# Main_Board.net
KiCad netlist of a schematic drawn in EAGLE
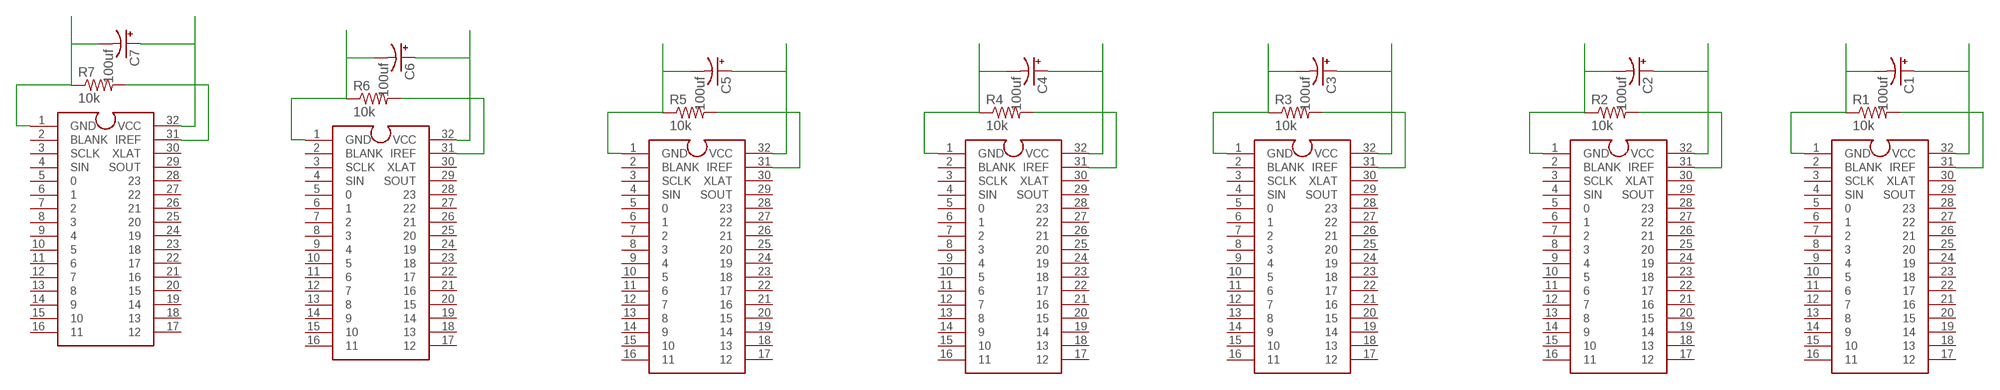
[diagram p0: schematic, sheet 1]

(export (version "E")
  (design (tool "Eeschema 10.0.6"))
  (components
    (comp (ref "C1")
      (value "100uf")
      (footprint "eagle-import:E2,5-6")
      (libsource (lib "eagle-import") (part "CPOL-USE2.5-6"))
    )
    (comp (ref "C2")
      (value "100uf")
      (footprint "eagle-import:E2,5-6")
      (libsource (lib "eagle-import") (part "CPOL-USE2.5-6"))
    )
    (comp (ref "C3")
      (value "100uf")
      (footprint "eagle-import:E2,5-6")
      (libsource (lib "eagle-import") (part "CPOL-USE2.5-6"))
    )
    (comp (ref "C4")
      (value "100uf")
      (footprint "eagle-import:E2,5-6")
      (libsource (lib "eagle-import") (part "CPOL-USE2.5-6"))
    )
    (comp (ref "C5")
      (value "100uf")
      (footprint "eagle-import:E2,5-6")
      (libsource (lib "eagle-import") (part "CPOL-USE2.5-6"))
    )
    (comp (ref "C6")
      (value "100uf")
      (footprint "eagle-import:E2,5-6")
      (libsource (lib "eagle-import") (part "CPOL-USE2.5-6"))
    )
    (comp (ref "C7")
      (value "100uf")
      (footprint "eagle-import:E2,5-6")
      (libsource (lib "eagle-import") (part "CPOL-USE2.5-6"))
    )
    (comp (ref "R1")
      (value "10k")
      (footprint "eagle-import:0207_10")
      (libsource (lib "eagle-import") (part "R-US_0207/10"))
    )
    (comp (ref "R2")
      (value "10k")
      (footprint "eagle-import:0207_10")
      (libsource (lib "eagle-import") (part "R-US_0207/10"))
    )
    (comp (ref "R3")
      (value "10k")
      (footprint "eagle-import:0207_10")
      (libsource (lib "eagle-import") (part "R-US_0207/10"))
    )
    (comp (ref "R4")
      (value "10k")
      (footprint "eagle-import:0207_10")
      (libsource (lib "eagle-import") (part "R-US_0207/10"))
    )
    (comp (ref "R5")
      (value "10k")
      (footprint "eagle-import:0207_10")
      (libsource (lib "eagle-import") (part "R-US_0207/10"))
    )
    (comp (ref "R6")
      (value "10k")
      (footprint "eagle-import:0207_10")
      (libsource (lib "eagle-import") (part "R-US_0207/10"))
    )
    (comp (ref "R7")
      (value "10k")
      (footprint "eagle-import:0207_10")
      (libsource (lib "eagle-import") (part "R-US_0207/10"))
    )
    (comp (ref "U$1")
      (value "TLC5947DAC")
      (footprint "eagle-import:DAP38")
      (libsource (lib "eagle-import") (part "TLC5947DAC"))
    )
    (comp (ref "U$2")
      (value "TLC5947DAC")
      (footprint "eagle-import:DAP38")
      (libsource (lib "eagle-import") (part "TLC5947DAC"))
    )
    (comp (ref "U$3")
      (value "TLC5947DAC")
      (footprint "eagle-import:DAP38")
      (libsource (lib "eagle-import") (part "TLC5947DAC"))
    )
    (comp (ref "U$4")
      (value "TLC5947DAC")
      (footprint "eagle-import:DAP38")
      (libsource (lib "eagle-import") (part "TLC5947DAC"))
    )
    (comp (ref "U$5")
      (value "TLC5947DAC")
      (footprint "eagle-import:DAP38")
      (libsource (lib "eagle-import") (part "TLC5947DAC"))
    )
    (comp (ref "U$6")
      (value "TLC5947DAC")
      (footprint "eagle-import:DAP38")
      (libsource (lib "eagle-import") (part "TLC5947DAC"))
    )
    (comp (ref "U$7")
      (value "TLC5947DAC")
      (footprint "eagle-import:DAP38")
      (libsource (lib "eagle-import") (part "TLC5947DAC"))
    )
  )
  (nets
    (net (code "1") (name "Net-(U$1-GND)") (class "Default")
      (node (ref "C1") (pin "-") (pinfunction "-_-") (pintype "passive"))
      (node (ref "R1") (pin "1") (pinfunction "1_1") (pintype "passive"))
      (node (ref "U$1") (pin "1") (pinfunction "GND_1") (pintype "bidirectional"))
    )
    (net (code "2") (name "Net-(U$1-IREF)") (class "Default")
      (node (ref "R1") (pin "2") (pinfunction "2_2") (pintype "passive"))
      (node (ref "U$1") (pin "31") (pinfunction "IREF_31") (pintype "bidirectional"))
    )
    (net (code "3") (name "Net-(U$1-VCC)") (class "Default")
      (node (ref "C1") (pin "+") (pinfunction "+_+") (pintype "passive"))
      (node (ref "U$1") (pin "32") (pinfunction "VCC_32") (pintype "bidirectional"))
    )
    (net (code "4") (name "Net-(U$2-GND)") (class "Default")
      (node (ref "C2") (pin "-") (pinfunction "-_-") (pintype "passive"))
      (node (ref "R2") (pin "1") (pinfunction "1_1") (pintype "passive"))
      (node (ref "U$2") (pin "1") (pinfunction "GND_1") (pintype "bidirectional"))
    )
    (net (code "5") (name "Net-(U$2-IREF)") (class "Default")
      (node (ref "R2") (pin "2") (pinfunction "2_2") (pintype "passive"))
      (node (ref "U$2") (pin "31") (pinfunction "IREF_31") (pintype "bidirectional"))
    )
    (net (code "6") (name "Net-(U$2-VCC)") (class "Default")
      (node (ref "C2") (pin "+") (pinfunction "+_+") (pintype "passive"))
      (node (ref "U$2") (pin "32") (pinfunction "VCC_32") (pintype "bidirectional"))
    )
    (net (code "7") (name "Net-(U$3-GND)") (class "Default")
      (node (ref "C3") (pin "-") (pinfunction "-_-") (pintype "passive"))
      (node (ref "R3") (pin "1") (pinfunction "1_1") (pintype "passive"))
      (node (ref "U$3") (pin "1") (pinfunction "GND_1") (pintype "bidirectional"))
    )
    (net (code "8") (name "Net-(U$3-IREF)") (class "Default")
      (node (ref "R3") (pin "2") (pinfunction "2_2") (pintype "passive"))
      (node (ref "U$3") (pin "31") (pinfunction "IREF_31") (pintype "bidirectional"))
    )
    (net (code "9") (name "Net-(U$3-VCC)") (class "Default")
      (node (ref "C3") (pin "+") (pinfunction "+_+") (pintype "passive"))
      (node (ref "U$3") (pin "32") (pinfunction "VCC_32") (pintype "bidirectional"))
    )
    (net (code "10") (name "Net-(U$4-GND)") (class "Default")
      (node (ref "C4") (pin "-") (pinfunction "-_-") (pintype "passive"))
      (node (ref "R4") (pin "1") (pinfunction "1_1") (pintype "passive"))
      (node (ref "U$4") (pin "1") (pinfunction "GND_1") (pintype "bidirectional"))
    )
    (net (code "11") (name "Net-(U$4-IREF)") (class "Default")
      (node (ref "R4") (pin "2") (pinfunction "2_2") (pintype "passive"))
      (node (ref "U$4") (pin "31") (pinfunction "IREF_31") (pintype "bidirectional"))
    )
    (net (code "12") (name "Net-(U$4-VCC)") (class "Default")
      (node (ref "C4") (pin "+") (pinfunction "+_+") (pintype "passive"))
      (node (ref "U$4") (pin "32") (pinfunction "VCC_32") (pintype "bidirectional"))
    )
    (net (code "13") (name "Net-(U$5-GND)") (class "Default")
      (node (ref "C5") (pin "-") (pinfunction "-_-") (pintype "passive"))
      (node (ref "R5") (pin "1") (pinfunction "1_1") (pintype "passive"))
      (node (ref "U$5") (pin "1") (pinfunction "GND_1") (pintype "bidirectional"))
    )
    (net (code "14") (name "Net-(U$5-IREF)") (class "Default")
      (node (ref "R5") (pin "2") (pinfunction "2_2") (pintype "passive"))
      (node (ref "U$5") (pin "31") (pinfunction "IREF_31") (pintype "bidirectional"))
    )
    (net (code "15") (name "Net-(U$5-VCC)") (class "Default")
      (node (ref "C5") (pin "+") (pinfunction "+_+") (pintype "passive"))
      (node (ref "U$5") (pin "32") (pinfunction "VCC_32") (pintype "bidirectional"))
    )
    (net (code "16") (name "Net-(U$6-GND)") (class "Default")
      (node (ref "C6") (pin "-") (pinfunction "-_-") (pintype "passive"))
      (node (ref "R6") (pin "1") (pinfunction "1_1") (pintype "passive"))
      (node (ref "U$6") (pin "1") (pinfunction "GND_1") (pintype "bidirectional"))
    )
    (net (code "17") (name "Net-(U$6-IREF)") (class "Default")
      (node (ref "R6") (pin "2") (pinfunction "2_2") (pintype "passive"))
      (node (ref "U$6") (pin "31") (pinfunction "IREF_31") (pintype "bidirectional"))
    )
    (net (code "18") (name "Net-(U$6-VCC)") (class "Default")
      (node (ref "C6") (pin "+") (pinfunction "+_+") (pintype "passive"))
      (node (ref "U$6") (pin "32") (pinfunction "VCC_32") (pintype "bidirectional"))
    )
    (net (code "19") (name "Net-(U$7-GND)") (class "Default")
      (node (ref "C7") (pin "-") (pinfunction "-_-") (pintype "passive"))
      (node (ref "R7") (pin "1") (pinfunction "1_1") (pintype "passive"))
      (node (ref "U$7") (pin "1") (pinfunction "GND_1") (pintype "bidirectional"))
    )
    (net (code "20") (name "Net-(U$7-IREF)") (class "Default")
      (node (ref "R7") (pin "2") (pinfunction "2_2") (pintype "passive"))
      (node (ref "U$7") (pin "31") (pinfunction "IREF_31") (pintype "bidirectional"))
    )
    (net (code "21") (name "Net-(U$7-VCC)") (class "Default")
      (node (ref "C7") (pin "+") (pinfunction "+_+") (pintype "passive"))
      (node (ref "U$7") (pin "32") (pinfunction "VCC_32") (pintype "bidirectional"))
    )
    (net (code "22") (name "unconnected-(U$1-0-Pad5)") (class "Default")
      (node (ref "U$1") (pin "5") (pinfunction "0_5") (pintype "bidirectional"))
    )
    (net (code "23") (name "unconnected-(U$1-1-Pad6)") (class "Default")
      (node (ref "U$1") (pin "6") (pinfunction "1_6") (pintype "bidirectional"))
    )
    (net (code "24") (name "unconnected-(U$1-2-Pad7)") (class "Default")
      (node (ref "U$1") (pin "7") (pinfunction "2_7") (pintype "bidirectional"))
    )
    (net (code "25") (name "unconnected-(U$1-3-Pad8)") (class "Default")
      (node (ref "U$1") (pin "8") (pinfunction "3_8") (pintype "bidirectional"))
    )
    (net (code "26") (name "unconnected-(U$1-4-Pad9)") (class "Default")
      (node (ref "U$1") (pin "9") (pinfunction "4_9") (pintype "bidirectional"))
    )
    (net (code "27") (name "unconnected-(U$1-5-Pad10)") (class "Default")
      (node (ref "U$1") (pin "10") (pinfunction "5_10") (pintype "bidirectional"))
    )
    (net (code "28") (name "unconnected-(U$1-6-Pad11)") (class "Default")
      (node (ref "U$1") (pin "11") (pinfunction "6_11") (pintype "bidirectional"))
    )
    (net (code "29") (name "unconnected-(U$1-7-Pad12)") (class "Default")
      (node (ref "U$1") (pin "12") (pinfunction "7_12") (pintype "bidirectional"))
    )
    (net (code "30") (name "unconnected-(U$1-8-Pad13)") (class "Default")
      (node (ref "U$1") (pin "13") (pinfunction "8_13") (pintype "bidirectional"))
    )
    (net (code "31") (name "unconnected-(U$1-9-Pad14)") (class "Default")
      (node (ref "U$1") (pin "14") (pinfunction "9_14") (pintype "bidirectional"))
    )
    (net (code "32") (name "unconnected-(U$1-10-Pad15)") (class "Default")
      (node (ref "U$1") (pin "15") (pinfunction "10_15") (pintype "bidirectional"))
    )
    (net (code "33") (name "unconnected-(U$1-11-Pad16)") (class "Default")
      (node (ref "U$1") (pin "16") (pinfunction "11_16") (pintype "bidirectional"))
    )
    (net (code "34") (name "unconnected-(U$1-12-Pad17)") (class "Default")
      (node (ref "U$1") (pin "17") (pinfunction "12_17") (pintype "bidirectional"))
    )
    (net (code "35") (name "unconnected-(U$1-13-Pad18)") (class "Default")
      (node (ref "U$1") (pin "18") (pinfunction "13_18") (pintype "bidirectional"))
    )
    (net (code "36") (name "unconnected-(U$1-14-Pad19)") (class "Default")
      (node (ref "U$1") (pin "19") (pinfunction "14_19") (pintype "bidirectional"))
    )
    (net (code "37") (name "unconnected-(U$1-15-Pad20)") (class "Default")
      (node (ref "U$1") (pin "20") (pinfunction "15_20") (pintype "bidirectional"))
    )
    (net (code "38") (name "unconnected-(U$1-16-Pad21)") (class "Default")
      (node (ref "U$1") (pin "21") (pinfunction "16_21") (pintype "bidirectional"))
    )
    (net (code "39") (name "unconnected-(U$1-17-Pad22)") (class "Default")
      (node (ref "U$1") (pin "22") (pinfunction "17_22") (pintype "bidirectional"))
    )
    (net (code "40") (name "unconnected-(U$1-18-Pad23)") (class "Default")
      (node (ref "U$1") (pin "23") (pinfunction "18_23") (pintype "bidirectional"))
    )
    (net (code "41") (name "unconnected-(U$1-19-Pad24)") (class "Default")
      (node (ref "U$1") (pin "24") (pinfunction "19_24") (pintype "bidirectional"))
    )
    (net (code "42") (name "unconnected-(U$1-20-Pad25)") (class "Default")
      (node (ref "U$1") (pin "25") (pinfunction "20_25") (pintype "bidirectional"))
    )
    (net (code "43") (name "unconnected-(U$1-21-Pad26)") (class "Default")
      (node (ref "U$1") (pin "26") (pinfunction "21_26") (pintype "bidirectional"))
    )
    (net (code "44") (name "unconnected-(U$1-22-Pad27)") (class "Default")
      (node (ref "U$1") (pin "27") (pinfunction "22_27") (pintype "bidirectional"))
    )
    (net (code "45") (name "unconnected-(U$1-23-Pad28)") (class "Default")
      (node (ref "U$1") (pin "28") (pinfunction "23_28") (pintype "bidirectional"))
    )
    (net (code "46") (name "unconnected-(U$1-BLANK-Pad2)") (class "Default")
      (node (ref "U$1") (pin "2") (pinfunction "BLANK_2") (pintype "bidirectional"))
    )
    (net (code "47") (name "unconnected-(U$1-SCLK-Pad3)") (class "Default")
      (node (ref "U$1") (pin "3") (pinfunction "SCLK_3") (pintype "bidirectional"))
    )
    (net (code "48") (name "unconnected-(U$1-SIN-Pad4)") (class "Default")
      (node (ref "U$1") (pin "4") (pinfunction "SIN_4") (pintype "bidirectional"))
    )
    (net (code "49") (name "unconnected-(U$1-SOUT-Pad29)") (class "Default")
      (node (ref "U$1") (pin "29") (pinfunction "SOUT_29") (pintype "bidirectional"))
    )
    (net (code "50") (name "unconnected-(U$1-XLAT-Pad30)") (class "Default")
      (node (ref "U$1") (pin "30") (pinfunction "XLAT_30") (pintype "bidirectional"))
    )
    (net (code "51") (name "unconnected-(U$2-0-Pad5)") (class "Default")
      (node (ref "U$2") (pin "5") (pinfunction "0_5") (pintype "bidirectional"))
    )
    (net (code "52") (name "unconnected-(U$2-1-Pad6)") (class "Default")
      (node (ref "U$2") (pin "6") (pinfunction "1_6") (pintype "bidirectional"))
    )
    (net (code "53") (name "unconnected-(U$2-2-Pad7)") (class "Default")
      (node (ref "U$2") (pin "7") (pinfunction "2_7") (pintype "bidirectional"))
    )
    (net (code "54") (name "unconnected-(U$2-3-Pad8)") (class "Default")
      (node (ref "U$2") (pin "8") (pinfunction "3_8") (pintype "bidirectional"))
    )
    (net (code "55") (name "unconnected-(U$2-4-Pad9)") (class "Default")
      (node (ref "U$2") (pin "9") (pinfunction "4_9") (pintype "bidirectional"))
    )
    (net (code "56") (name "unconnected-(U$2-5-Pad10)") (class "Default")
      (node (ref "U$2") (pin "10") (pinfunction "5_10") (pintype "bidirectional"))
    )
    (net (code "57") (name "unconnected-(U$2-6-Pad11)") (class "Default")
      (node (ref "U$2") (pin "11") (pinfunction "6_11") (pintype "bidirectional"))
    )
    (net (code "58") (name "unconnected-(U$2-7-Pad12)") (class "Default")
      (node (ref "U$2") (pin "12") (pinfunction "7_12") (pintype "bidirectional"))
    )
    (net (code "59") (name "unconnected-(U$2-8-Pad13)") (class "Default")
      (node (ref "U$2") (pin "13") (pinfunction "8_13") (pintype "bidirectional"))
    )
    (net (code "60") (name "unconnected-(U$2-9-Pad14)") (class "Default")
      (node (ref "U$2") (pin "14") (pinfunction "9_14") (pintype "bidirectional"))
    )
    (net (code "61") (name "unconnected-(U$2-10-Pad15)") (class "Default")
      (node (ref "U$2") (pin "15") (pinfunction "10_15") (pintype "bidirectional"))
    )
    (net (code "62") (name "unconnected-(U$2-11-Pad16)") (class "Default")
      (node (ref "U$2") (pin "16") (pinfunction "11_16") (pintype "bidirectional"))
    )
    (net (code "63") (name "unconnected-(U$2-12-Pad17)") (class "Default")
      (node (ref "U$2") (pin "17") (pinfunction "12_17") (pintype "bidirectional"))
    )
    (net (code "64") (name "unconnected-(U$2-13-Pad18)") (class "Default")
      (node (ref "U$2") (pin "18") (pinfunction "13_18") (pintype "bidirectional"))
    )
    (net (code "65") (name "unconnected-(U$2-14-Pad19)") (class "Default")
      (node (ref "U$2") (pin "19") (pinfunction "14_19") (pintype "bidirectional"))
    )
    (net (code "66") (name "unconnected-(U$2-15-Pad20)") (class "Default")
      (node (ref "U$2") (pin "20") (pinfunction "15_20") (pintype "bidirectional"))
    )
    (net (code "67") (name "unconnected-(U$2-16-Pad21)") (class "Default")
      (node (ref "U$2") (pin "21") (pinfunction "16_21") (pintype "bidirectional"))
    )
    (net (code "68") (name "unconnected-(U$2-17-Pad22)") (class "Default")
      (node (ref "U$2") (pin "22") (pinfunction "17_22") (pintype "bidirectional"))
    )
    (net (code "69") (name "unconnected-(U$2-18-Pad23)") (class "Default")
      (node (ref "U$2") (pin "23") (pinfunction "18_23") (pintype "bidirectional"))
    )
    (net (code "70") (name "unconnected-(U$2-19-Pad24)") (class "Default")
      (node (ref "U$2") (pin "24") (pinfunction "19_24") (pintype "bidirectional"))
    )
    (net (code "71") (name "unconnected-(U$2-20-Pad25)") (class "Default")
      (node (ref "U$2") (pin "25") (pinfunction "20_25") (pintype "bidirectional"))
    )
    (net (code "72") (name "unconnected-(U$2-21-Pad26)") (class "Default")
      (node (ref "U$2") (pin "26") (pinfunction "21_26") (pintype "bidirectional"))
    )
    (net (code "73") (name "unconnected-(U$2-22-Pad27)") (class "Default")
      (node (ref "U$2") (pin "27") (pinfunction "22_27") (pintype "bidirectional"))
    )
    (net (code "74") (name "unconnected-(U$2-23-Pad28)") (class "Default")
      (node (ref "U$2") (pin "28") (pinfunction "23_28") (pintype "bidirectional"))
    )
    (net (code "75") (name "unconnected-(U$2-BLANK-Pad2)") (class "Default")
      (node (ref "U$2") (pin "2") (pinfunction "BLANK_2") (pintype "bidirectional"))
    )
    (net (code "76") (name "unconnected-(U$2-SCLK-Pad3)") (class "Default")
      (node (ref "U$2") (pin "3") (pinfunction "SCLK_3") (pintype "bidirectional"))
    )
    (net (code "77") (name "unconnected-(U$2-SIN-Pad4)") (class "Default")
      (node (ref "U$2") (pin "4") (pinfunction "SIN_4") (pintype "bidirectional"))
    )
    (net (code "78") (name "unconnected-(U$2-SOUT-Pad29)") (class "Default")
      (node (ref "U$2") (pin "29") (pinfunction "SOUT_29") (pintype "bidirectional"))
    )
    (net (code "79") (name "unconnected-(U$2-XLAT-Pad30)") (class "Default")
      (node (ref "U$2") (pin "30") (pinfunction "XLAT_30") (pintype "bidirectional"))
    )
    (net (code "80") (name "unconnected-(U$3-0-Pad5)") (class "Default")
      (node (ref "U$3") (pin "5") (pinfunction "0_5") (pintype "bidirectional"))
    )
    (net (code "81") (name "unconnected-(U$3-1-Pad6)") (class "Default")
      (node (ref "U$3") (pin "6") (pinfunction "1_6") (pintype "bidirectional"))
    )
    (net (code "82") (name "unconnected-(U$3-2-Pad7)") (class "Default")
      (node (ref "U$3") (pin "7") (pinfunction "2_7") (pintype "bidirectional"))
    )
    (net (code "83") (name "unconnected-(U$3-3-Pad8)") (class "Default")
      (node (ref "U$3") (pin "8") (pinfunction "3_8") (pintype "bidirectional"))
    )
    (net (code "84") (name "unconnected-(U$3-4-Pad9)") (class "Default")
      (node (ref "U$3") (pin "9") (pinfunction "4_9") (pintype "bidirectional"))
    )
    (net (code "85") (name "unconnected-(U$3-5-Pad10)") (class "Default")
      (node (ref "U$3") (pin "10") (pinfunction "5_10") (pintype "bidirectional"))
    )
    (net (code "86") (name "unconnected-(U$3-6-Pad11)") (class "Default")
      (node (ref "U$3") (pin "11") (pinfunction "6_11") (pintype "bidirectional"))
    )
    (net (code "87") (name "unconnected-(U$3-7-Pad12)") (class "Default")
      (node (ref "U$3") (pin "12") (pinfunction "7_12") (pintype "bidirectional"))
    )
    (net (code "88") (name "unconnected-(U$3-8-Pad13)") (class "Default")
      (node (ref "U$3") (pin "13") (pinfunction "8_13") (pintype "bidirectional"))
    )
    (net (code "89") (name "unconnected-(U$3-9-Pad14)") (class "Default")
      (node (ref "U$3") (pin "14") (pinfunction "9_14") (pintype "bidirectional"))
    )
    (net (code "90") (name "unconnected-(U$3-10-Pad15)") (class "Default")
      (node (ref "U$3") (pin "15") (pinfunction "10_15") (pintype "bidirectional"))
    )
    (net (code "91") (name "unconnected-(U$3-11-Pad16)") (class "Default")
      (node (ref "U$3") (pin "16") (pinfunction "11_16") (pintype "bidirectional"))
    )
    (net (code "92") (name "unconnected-(U$3-12-Pad17)") (class "Default")
      (node (ref "U$3") (pin "17") (pinfunction "12_17") (pintype "bidirectional"))
    )
    (net (code "93") (name "unconnected-(U$3-13-Pad18)") (class "Default")
      (node (ref "U$3") (pin "18") (pinfunction "13_18") (pintype "bidirectional"))
    )
    (net (code "94") (name "unconnected-(U$3-14-Pad19)") (class "Default")
      (node (ref "U$3") (pin "19") (pinfunction "14_19") (pintype "bidirectional"))
    )
    (net (code "95") (name "unconnected-(U$3-15-Pad20)") (class "Default")
      (node (ref "U$3") (pin "20") (pinfunction "15_20") (pintype "bidirectional"))
    )
    (net (code "96") (name "unconnected-(U$3-16-Pad21)") (class "Default")
      (node (ref "U$3") (pin "21") (pinfunction "16_21") (pintype "bidirectional"))
    )
    (net (code "97") (name "unconnected-(U$3-17-Pad22)") (class "Default")
      (node (ref "U$3") (pin "22") (pinfunction "17_22") (pintype "bidirectional"))
    )
    (net (code "98") (name "unconnected-(U$3-18-Pad23)") (class "Default")
      (node (ref "U$3") (pin "23") (pinfunction "18_23") (pintype "bidirectional"))
    )
    (net (code "99") (name "unconnected-(U$3-19-Pad24)") (class "Default")
      (node (ref "U$3") (pin "24") (pinfunction "19_24") (pintype "bidirectional"))
    )
    (net (code "100") (name "unconnected-(U$3-20-Pad25)") (class "Default")
      (node (ref "U$3") (pin "25") (pinfunction "20_25") (pintype "bidirectional"))
    )
    (net (code "101") (name "unconnected-(U$3-21-Pad26)") (class "Default")
      (node (ref "U$3") (pin "26") (pinfunction "21_26") (pintype "bidirectional"))
    )
    (net (code "102") (name "unconnected-(U$3-22-Pad27)") (class "Default")
      (node (ref "U$3") (pin "27") (pinfunction "22_27") (pintype "bidirectional"))
    )
    (net (code "103") (name "unconnected-(U$3-23-Pad28)") (class "Default")
      (node (ref "U$3") (pin "28") (pinfunction "23_28") (pintype "bidirectional"))
    )
    (net (code "104") (name "unconnected-(U$3-BLANK-Pad2)") (class "Default")
      (node (ref "U$3") (pin "2") (pinfunction "BLANK_2") (pintype "bidirectional"))
    )
    (net (code "105") (name "unconnected-(U$3-SCLK-Pad3)") (class "Default")
      (node (ref "U$3") (pin "3") (pinfunction "SCLK_3") (pintype "bidirectional"))
    )
    (net (code "106") (name "unconnected-(U$3-SIN-Pad4)") (class "Default")
      (node (ref "U$3") (pin "4") (pinfunction "SIN_4") (pintype "bidirectional"))
    )
    (net (code "107") (name "unconnected-(U$3-SOUT-Pad29)") (class "Default")
      (node (ref "U$3") (pin "29") (pinfunction "SOUT_29") (pintype "bidirectional"))
    )
    (net (code "108") (name "unconnected-(U$3-XLAT-Pad30)") (class "Default")
      (node (ref "U$3") (pin "30") (pinfunction "XLAT_30") (pintype "bidirectional"))
    )
    (net (code "109") (name "unconnected-(U$4-0-Pad5)") (class "Default")
      (node (ref "U$4") (pin "5") (pinfunction "0_5") (pintype "bidirectional"))
    )
    (net (code "110") (name "unconnected-(U$4-1-Pad6)") (class "Default")
      (node (ref "U$4") (pin "6") (pinfunction "1_6") (pintype "bidirectional"))
    )
    (net (code "111") (name "unconnected-(U$4-2-Pad7)") (class "Default")
      (node (ref "U$4") (pin "7") (pinfunction "2_7") (pintype "bidirectional"))
    )
    (net (code "112") (name "unconnected-(U$4-3-Pad8)") (class "Default")
      (node (ref "U$4") (pin "8") (pinfunction "3_8") (pintype "bidirectional"))
    )
    (net (code "113") (name "unconnected-(U$4-4-Pad9)") (class "Default")
      (node (ref "U$4") (pin "9") (pinfunction "4_9") (pintype "bidirectional"))
    )
    (net (code "114") (name "unconnected-(U$4-5-Pad10)") (class "Default")
      (node (ref "U$4") (pin "10") (pinfunction "5_10") (pintype "bidirectional"))
    )
    (net (code "115") (name "unconnected-(U$4-6-Pad11)") (class "Default")
      (node (ref "U$4") (pin "11") (pinfunction "6_11") (pintype "bidirectional"))
    )
    (net (code "116") (name "unconnected-(U$4-7-Pad12)") (class "Default")
      (node (ref "U$4") (pin "12") (pinfunction "7_12") (pintype "bidirectional"))
    )
    (net (code "117") (name "unconnected-(U$4-8-Pad13)") (class "Default")
      (node (ref "U$4") (pin "13") (pinfunction "8_13") (pintype "bidirectional"))
    )
    (net (code "118") (name "unconnected-(U$4-9-Pad14)") (class "Default")
      (node (ref "U$4") (pin "14") (pinfunction "9_14") (pintype "bidirectional"))
    )
    (net (code "119") (name "unconnected-(U$4-10-Pad15)") (class "Default")
      (node (ref "U$4") (pin "15") (pinfunction "10_15") (pintype "bidirectional"))
    )
    (net (code "120") (name "unconnected-(U$4-11-Pad16)") (class "Default")
      (node (ref "U$4") (pin "16") (pinfunction "11_16") (pintype "bidirectional"))
    )
    (net (code "121") (name "unconnected-(U$4-12-Pad17)") (class "Default")
      (node (ref "U$4") (pin "17") (pinfunction "12_17") (pintype "bidirectional"))
    )
    (net (code "122") (name "unconnected-(U$4-13-Pad18)") (class "Default")
      (node (ref "U$4") (pin "18") (pinfunction "13_18") (pintype "bidirectional"))
    )
    (net (code "123") (name "unconnected-(U$4-14-Pad19)") (class "Default")
      (node (ref "U$4") (pin "19") (pinfunction "14_19") (pintype "bidirectional"))
    )
    (net (code "124") (name "unconnected-(U$4-15-Pad20)") (class "Default")
      (node (ref "U$4") (pin "20") (pinfunction "15_20") (pintype "bidirectional"))
    )
    (net (code "125") (name "unconnected-(U$4-16-Pad21)") (class "Default")
      (node (ref "U$4") (pin "21") (pinfunction "16_21") (pintype "bidirectional"))
    )
    (net (code "126") (name "unconnected-(U$4-17-Pad22)") (class "Default")
      (node (ref "U$4") (pin "22") (pinfunction "17_22") (pintype "bidirectional"))
    )
    (net (code "127") (name "unconnected-(U$4-18-Pad23)") (class "Default")
      (node (ref "U$4") (pin "23") (pinfunction "18_23") (pintype "bidirectional"))
    )
    (net (code "128") (name "unconnected-(U$4-19-Pad24)") (class "Default")
      (node (ref "U$4") (pin "24") (pinfunction "19_24") (pintype "bidirectional"))
    )
    (net (code "129") (name "unconnected-(U$4-20-Pad25)") (class "Default")
      (node (ref "U$4") (pin "25") (pinfunction "20_25") (pintype "bidirectional"))
    )
    (net (code "130") (name "unconnected-(U$4-21-Pad26)") (class "Default")
      (node (ref "U$4") (pin "26") (pinfunction "21_26") (pintype "bidirectional"))
    )
    (net (code "131") (name "unconnected-(U$4-22-Pad27)") (class "Default")
      (node (ref "U$4") (pin "27") (pinfunction "22_27") (pintype "bidirectional"))
    )
    (net (code "132") (name "unconnected-(U$4-23-Pad28)") (class "Default")
      (node (ref "U$4") (pin "28") (pinfunction "23_28") (pintype "bidirectional"))
    )
    (net (code "133") (name "unconnected-(U$4-BLANK-Pad2)") (class "Default")
      (node (ref "U$4") (pin "2") (pinfunction "BLANK_2") (pintype "bidirectional"))
    )
    (net (code "134") (name "unconnected-(U$4-SCLK-Pad3)") (class "Default")
      (node (ref "U$4") (pin "3") (pinfunction "SCLK_3") (pintype "bidirectional"))
    )
    (net (code "135") (name "unconnected-(U$4-SIN-Pad4)") (class "Default")
      (node (ref "U$4") (pin "4") (pinfunction "SIN_4") (pintype "bidirectional"))
    )
    (net (code "136") (name "unconnected-(U$4-SOUT-Pad29)") (class "Default")
      (node (ref "U$4") (pin "29") (pinfunction "SOUT_29") (pintype "bidirectional"))
    )
    (net (code "137") (name "unconnected-(U$4-XLAT-Pad30)") (class "Default")
      (node (ref "U$4") (pin "30") (pinfunction "XLAT_30") (pintype "bidirectional"))
    )
    (net (code "138") (name "unconnected-(U$5-0-Pad5)") (class "Default")
      (node (ref "U$5") (pin "5") (pinfunction "0_5") (pintype "bidirectional"))
    )
    (net (code "139") (name "unconnected-(U$5-1-Pad6)") (class "Default")
      (node (ref "U$5") (pin "6") (pinfunction "1_6") (pintype "bidirectional"))
    )
    (net (code "140") (name "unconnected-(U$5-2-Pad7)") (class "Default")
      (node (ref "U$5") (pin "7") (pinfunction "2_7") (pintype "bidirectional"))
    )
    (net (code "141") (name "unconnected-(U$5-3-Pad8)") (class "Default")
      (node (ref "U$5") (pin "8") (pinfunction "3_8") (pintype "bidirectional"))
    )
    (net (code "142") (name "unconnected-(U$5-4-Pad9)") (class "Default")
      (node (ref "U$5") (pin "9") (pinfunction "4_9") (pintype "bidirectional"))
    )
    (net (code "143") (name "unconnected-(U$5-5-Pad10)") (class "Default")
      (node (ref "U$5") (pin "10") (pinfunction "5_10") (pintype "bidirectional"))
    )
    (net (code "144") (name "unconnected-(U$5-6-Pad11)") (class "Default")
      (node (ref "U$5") (pin "11") (pinfunction "6_11") (pintype "bidirectional"))
    )
    (net (code "145") (name "unconnected-(U$5-7-Pad12)") (class "Default")
      (node (ref "U$5") (pin "12") (pinfunction "7_12") (pintype "bidirectional"))
    )
    (net (code "146") (name "unconnected-(U$5-8-Pad13)") (class "Default")
      (node (ref "U$5") (pin "13") (pinfunction "8_13") (pintype "bidirectional"))
    )
    (net (code "147") (name "unconnected-(U$5-9-Pad14)") (class "Default")
      (node (ref "U$5") (pin "14") (pinfunction "9_14") (pintype "bidirectional"))
    )
    (net (code "148") (name "unconnected-(U$5-10-Pad15)") (class "Default")
      (node (ref "U$5") (pin "15") (pinfunction "10_15") (pintype "bidirectional"))
    )
    (net (code "149") (name "unconnected-(U$5-11-Pad16)") (class "Default")
      (node (ref "U$5") (pin "16") (pinfunction "11_16") (pintype "bidirectional"))
    )
    (net (code "150") (name "unconnected-(U$5-12-Pad17)") (class "Default")
      (node (ref "U$5") (pin "17") (pinfunction "12_17") (pintype "bidirectional"))
    )
    (net (code "151") (name "unconnected-(U$5-13-Pad18)") (class "Default")
      (node (ref "U$5") (pin "18") (pinfunction "13_18") (pintype "bidirectional"))
    )
    (net (code "152") (name "unconnected-(U$5-14-Pad19)") (class "Default")
      (node (ref "U$5") (pin "19") (pinfunction "14_19") (pintype "bidirectional"))
    )
    (net (code "153") (name "unconnected-(U$5-15-Pad20)") (class "Default")
      (node (ref "U$5") (pin "20") (pinfunction "15_20") (pintype "bidirectional"))
    )
    (net (code "154") (name "unconnected-(U$5-16-Pad21)") (class "Default")
      (node (ref "U$5") (pin "21") (pinfunction "16_21") (pintype "bidirectional"))
    )
    (net (code "155") (name "unconnected-(U$5-17-Pad22)") (class "Default")
      (node (ref "U$5") (pin "22") (pinfunction "17_22") (pintype "bidirectional"))
    )
    (net (code "156") (name "unconnected-(U$5-18-Pad23)") (class "Default")
      (node (ref "U$5") (pin "23") (pinfunction "18_23") (pintype "bidirectional"))
    )
    (net (code "157") (name "unconnected-(U$5-19-Pad24)") (class "Default")
      (node (ref "U$5") (pin "24") (pinfunction "19_24") (pintype "bidirectional"))
    )
    (net (code "158") (name "unconnected-(U$5-20-Pad25)") (class "Default")
      (node (ref "U$5") (pin "25") (pinfunction "20_25") (pintype "bidirectional"))
    )
    (net (code "159") (name "unconnected-(U$5-21-Pad26)") (class "Default")
      (node (ref "U$5") (pin "26") (pinfunction "21_26") (pintype "bidirectional"))
    )
    (net (code "160") (name "unconnected-(U$5-22-Pad27)") (class "Default")
      (node (ref "U$5") (pin "27") (pinfunction "22_27") (pintype "bidirectional"))
    )
    (net (code "161") (name "unconnected-(U$5-23-Pad28)") (class "Default")
      (node (ref "U$5") (pin "28") (pinfunction "23_28") (pintype "bidirectional"))
    )
    (net (code "162") (name "unconnected-(U$5-BLANK-Pad2)") (class "Default")
      (node (ref "U$5") (pin "2") (pinfunction "BLANK_2") (pintype "bidirectional"))
    )
    (net (code "163") (name "unconnected-(U$5-SCLK-Pad3)") (class "Default")
      (node (ref "U$5") (pin "3") (pinfunction "SCLK_3") (pintype "bidirectional"))
    )
    (net (code "164") (name "unconnected-(U$5-SIN-Pad4)") (class "Default")
      (node (ref "U$5") (pin "4") (pinfunction "SIN_4") (pintype "bidirectional"))
    )
    (net (code "165") (name "unconnected-(U$5-SOUT-Pad29)") (class "Default")
      (node (ref "U$5") (pin "29") (pinfunction "SOUT_29") (pintype "bidirectional"))
    )
    (net (code "166") (name "unconnected-(U$5-XLAT-Pad30)") (class "Default")
      (node (ref "U$5") (pin "30") (pinfunction "XLAT_30") (pintype "bidirectional"))
    )
    (net (code "167") (name "unconnected-(U$6-0-Pad5)") (class "Default")
      (node (ref "U$6") (pin "5") (pinfunction "0_5") (pintype "bidirectional"))
    )
    (net (code "168") (name "unconnected-(U$6-1-Pad6)") (class "Default")
      (node (ref "U$6") (pin "6") (pinfunction "1_6") (pintype "bidirectional"))
    )
    (net (code "169") (name "unconnected-(U$6-2-Pad7)") (class "Default")
      (node (ref "U$6") (pin "7") (pinfunction "2_7") (pintype "bidirectional"))
    )
    (net (code "170") (name "unconnected-(U$6-3-Pad8)") (class "Default")
      (node (ref "U$6") (pin "8") (pinfunction "3_8") (pintype "bidirectional"))
    )
    (net (code "171") (name "unconnected-(U$6-4-Pad9)") (class "Default")
      (node (ref "U$6") (pin "9") (pinfunction "4_9") (pintype "bidirectional"))
    )
    (net (code "172") (name "unconnected-(U$6-5-Pad10)") (class "Default")
      (node (ref "U$6") (pin "10") (pinfunction "5_10") (pintype "bidirectional"))
    )
    (net (code "173") (name "unconnected-(U$6-6-Pad11)") (class "Default")
      (node (ref "U$6") (pin "11") (pinfunction "6_11") (pintype "bidirectional"))
    )
    (net (code "174") (name "unconnected-(U$6-7-Pad12)") (class "Default")
      (node (ref "U$6") (pin "12") (pinfunction "7_12") (pintype "bidirectional"))
    )
    (net (code "175") (name "unconnected-(U$6-8-Pad13)") (class "Default")
      (node (ref "U$6") (pin "13") (pinfunction "8_13") (pintype "bidirectional"))
    )
    (net (code "176") (name "unconnected-(U$6-9-Pad14)") (class "Default")
      (node (ref "U$6") (pin "14") (pinfunction "9_14") (pintype "bidirectional"))
    )
    (net (code "177") (name "unconnected-(U$6-10-Pad15)") (class "Default")
      (node (ref "U$6") (pin "15") (pinfunction "10_15") (pintype "bidirectional"))
    )
    (net (code "178") (name "unconnected-(U$6-11-Pad16)") (class "Default")
      (node (ref "U$6") (pin "16") (pinfunction "11_16") (pintype "bidirectional"))
    )
    (net (code "179") (name "unconnected-(U$6-12-Pad17)") (class "Default")
      (node (ref "U$6") (pin "17") (pinfunction "12_17") (pintype "bidirectional"))
    )
    (net (code "180") (name "unconnected-(U$6-13-Pad18)") (class "Default")
      (node (ref "U$6") (pin "18") (pinfunction "13_18") (pintype "bidirectional"))
    )
    (net (code "181") (name "unconnected-(U$6-14-Pad19)") (class "Default")
      (node (ref "U$6") (pin "19") (pinfunction "14_19") (pintype "bidirectional"))
    )
    (net (code "182") (name "unconnected-(U$6-15-Pad20)") (class "Default")
      (node (ref "U$6") (pin "20") (pinfunction "15_20") (pintype "bidirectional"))
    )
    (net (code "183") (name "unconnected-(U$6-16-Pad21)") (class "Default")
      (node (ref "U$6") (pin "21") (pinfunction "16_21") (pintype "bidirectional"))
    )
    (net (code "184") (name "unconnected-(U$6-17-Pad22)") (class "Default")
      (node (ref "U$6") (pin "22") (pinfunction "17_22") (pintype "bidirectional"))
    )
    (net (code "185") (name "unconnected-(U$6-18-Pad23)") (class "Default")
      (node (ref "U$6") (pin "23") (pinfunction "18_23") (pintype "bidirectional"))
    )
    (net (code "186") (name "unconnected-(U$6-19-Pad24)") (class "Default")
      (node (ref "U$6") (pin "24") (pinfunction "19_24") (pintype "bidirectional"))
    )
    (net (code "187") (name "unconnected-(U$6-20-Pad25)") (class "Default")
      (node (ref "U$6") (pin "25") (pinfunction "20_25") (pintype "bidirectional"))
    )
    (net (code "188") (name "unconnected-(U$6-21-Pad26)") (class "Default")
      (node (ref "U$6") (pin "26") (pinfunction "21_26") (pintype "bidirectional"))
    )
    (net (code "189") (name "unconnected-(U$6-22-Pad27)") (class "Default")
      (node (ref "U$6") (pin "27") (pinfunction "22_27") (pintype "bidirectional"))
    )
    (net (code "190") (name "unconnected-(U$6-23-Pad28)") (class "Default")
      (node (ref "U$6") (pin "28") (pinfunction "23_28") (pintype "bidirectional"))
    )
    (net (code "191") (name "unconnected-(U$6-BLANK-Pad2)") (class "Default")
      (node (ref "U$6") (pin "2") (pinfunction "BLANK_2") (pintype "bidirectional"))
    )
    (net (code "192") (name "unconnected-(U$6-SCLK-Pad3)") (class "Default")
      (node (ref "U$6") (pin "3") (pinfunction "SCLK_3") (pintype "bidirectional"))
    )
    (net (code "193") (name "unconnected-(U$6-SIN-Pad4)") (class "Default")
      (node (ref "U$6") (pin "4") (pinfunction "SIN_4") (pintype "bidirectional"))
    )
    (net (code "194") (name "unconnected-(U$6-SOUT-Pad29)") (class "Default")
      (node (ref "U$6") (pin "29") (pinfunction "SOUT_29") (pintype "bidirectional"))
    )
    (net (code "195") (name "unconnected-(U$6-XLAT-Pad30)") (class "Default")
      (node (ref "U$6") (pin "30") (pinfunction "XLAT_30") (pintype "bidirectional"))
    )
    (net (code "196") (name "unconnected-(U$7-0-Pad5)") (class "Default")
      (node (ref "U$7") (pin "5") (pinfunction "0_5") (pintype "bidirectional"))
    )
    (net (code "197") (name "unconnected-(U$7-1-Pad6)") (class "Default")
      (node (ref "U$7") (pin "6") (pinfunction "1_6") (pintype "bidirectional"))
    )
    (net (code "198") (name "unconnected-(U$7-2-Pad7)") (class "Default")
      (node (ref "U$7") (pin "7") (pinfunction "2_7") (pintype "bidirectional"))
    )
    (net (code "199") (name "unconnected-(U$7-3-Pad8)") (class "Default")
      (node (ref "U$7") (pin "8") (pinfunction "3_8") (pintype "bidirectional"))
    )
    (net (code "200") (name "unconnected-(U$7-4-Pad9)") (class "Default")
      (node (ref "U$7") (pin "9") (pinfunction "4_9") (pintype "bidirectional"))
    )
    (net (code "201") (name "unconnected-(U$7-5-Pad10)") (class "Default")
      (node (ref "U$7") (pin "10") (pinfunction "5_10") (pintype "bidirectional"))
    )
    (net (code "202") (name "unconnected-(U$7-6-Pad11)") (class "Default")
      (node (ref "U$7") (pin "11") (pinfunction "6_11") (pintype "bidirectional"))
    )
    (net (code "203") (name "unconnected-(U$7-7-Pad12)") (class "Default")
      (node (ref "U$7") (pin "12") (pinfunction "7_12") (pintype "bidirectional"))
    )
    (net (code "204") (name "unconnected-(U$7-8-Pad13)") (class "Default")
      (node (ref "U$7") (pin "13") (pinfunction "8_13") (pintype "bidirectional"))
    )
    (net (code "205") (name "unconnected-(U$7-9-Pad14)") (class "Default")
      (node (ref "U$7") (pin "14") (pinfunction "9_14") (pintype "bidirectional"))
    )
    (net (code "206") (name "unconnected-(U$7-10-Pad15)") (class "Default")
      (node (ref "U$7") (pin "15") (pinfunction "10_15") (pintype "bidirectional"))
    )
    (net (code "207") (name "unconnected-(U$7-11-Pad16)") (class "Default")
      (node (ref "U$7") (pin "16") (pinfunction "11_16") (pintype "bidirectional"))
    )
    (net (code "208") (name "unconnected-(U$7-12-Pad17)") (class "Default")
      (node (ref "U$7") (pin "17") (pinfunction "12_17") (pintype "bidirectional"))
    )
    (net (code "209") (name "unconnected-(U$7-13-Pad18)") (class "Default")
      (node (ref "U$7") (pin "18") (pinfunction "13_18") (pintype "bidirectional"))
    )
    (net (code "210") (name "unconnected-(U$7-14-Pad19)") (class "Default")
      (node (ref "U$7") (pin "19") (pinfunction "14_19") (pintype "bidirectional"))
    )
    (net (code "211") (name "unconnected-(U$7-15-Pad20)") (class "Default")
      (node (ref "U$7") (pin "20") (pinfunction "15_20") (pintype "bidirectional"))
    )
    (net (code "212") (name "unconnected-(U$7-16-Pad21)") (class "Default")
      (node (ref "U$7") (pin "21") (pinfunction "16_21") (pintype "bidirectional"))
    )
    (net (code "213") (name "unconnected-(U$7-17-Pad22)") (class "Default")
      (node (ref "U$7") (pin "22") (pinfunction "17_22") (pintype "bidirectional"))
    )
    (net (code "214") (name "unconnected-(U$7-18-Pad23)") (class "Default")
      (node (ref "U$7") (pin "23") (pinfunction "18_23") (pintype "bidirectional"))
    )
    (net (code "215") (name "unconnected-(U$7-19-Pad24)") (class "Default")
      (node (ref "U$7") (pin "24") (pinfunction "19_24") (pintype "bidirectional"))
    )
    (net (code "216") (name "unconnected-(U$7-20-Pad25)") (class "Default")
      (node (ref "U$7") (pin "25") (pinfunction "20_25") (pintype "bidirectional"))
    )
    (net (code "217") (name "unconnected-(U$7-21-Pad26)") (class "Default")
      (node (ref "U$7") (pin "26") (pinfunction "21_26") (pintype "bidirectional"))
    )
    (net (code "218") (name "unconnected-(U$7-22-Pad27)") (class "Default")
      (node (ref "U$7") (pin "27") (pinfunction "22_27") (pintype "bidirectional"))
    )
    (net (code "219") (name "unconnected-(U$7-23-Pad28)") (class "Default")
      (node (ref "U$7") (pin "28") (pinfunction "23_28") (pintype "bidirectional"))
    )
    (net (code "220") (name "unconnected-(U$7-BLANK-Pad2)") (class "Default")
      (node (ref "U$7") (pin "2") (pinfunction "BLANK_2") (pintype "bidirectional"))
    )
    (net (code "221") (name "unconnected-(U$7-SCLK-Pad3)") (class "Default")
      (node (ref "U$7") (pin "3") (pinfunction "SCLK_3") (pintype "bidirectional"))
    )
    (net (code "222") (name "unconnected-(U$7-SIN-Pad4)") (class "Default")
      (node (ref "U$7") (pin "4") (pinfunction "SIN_4") (pintype "bidirectional"))
    )
    (net (code "223") (name "unconnected-(U$7-SOUT-Pad29)") (class "Default")
      (node (ref "U$7") (pin "29") (pinfunction "SOUT_29") (pintype "bidirectional"))
    )
    (net (code "224") (name "unconnected-(U$7-XLAT-Pad30)") (class "Default")
      (node (ref "U$7") (pin "30") (pinfunction "XLAT_30") (pintype "bidirectional"))
    )
  )
)
